# ModuleCarrier-Laird-BL600-v1_1.net
KiCad netlist of a schematic drawn in EAGLE
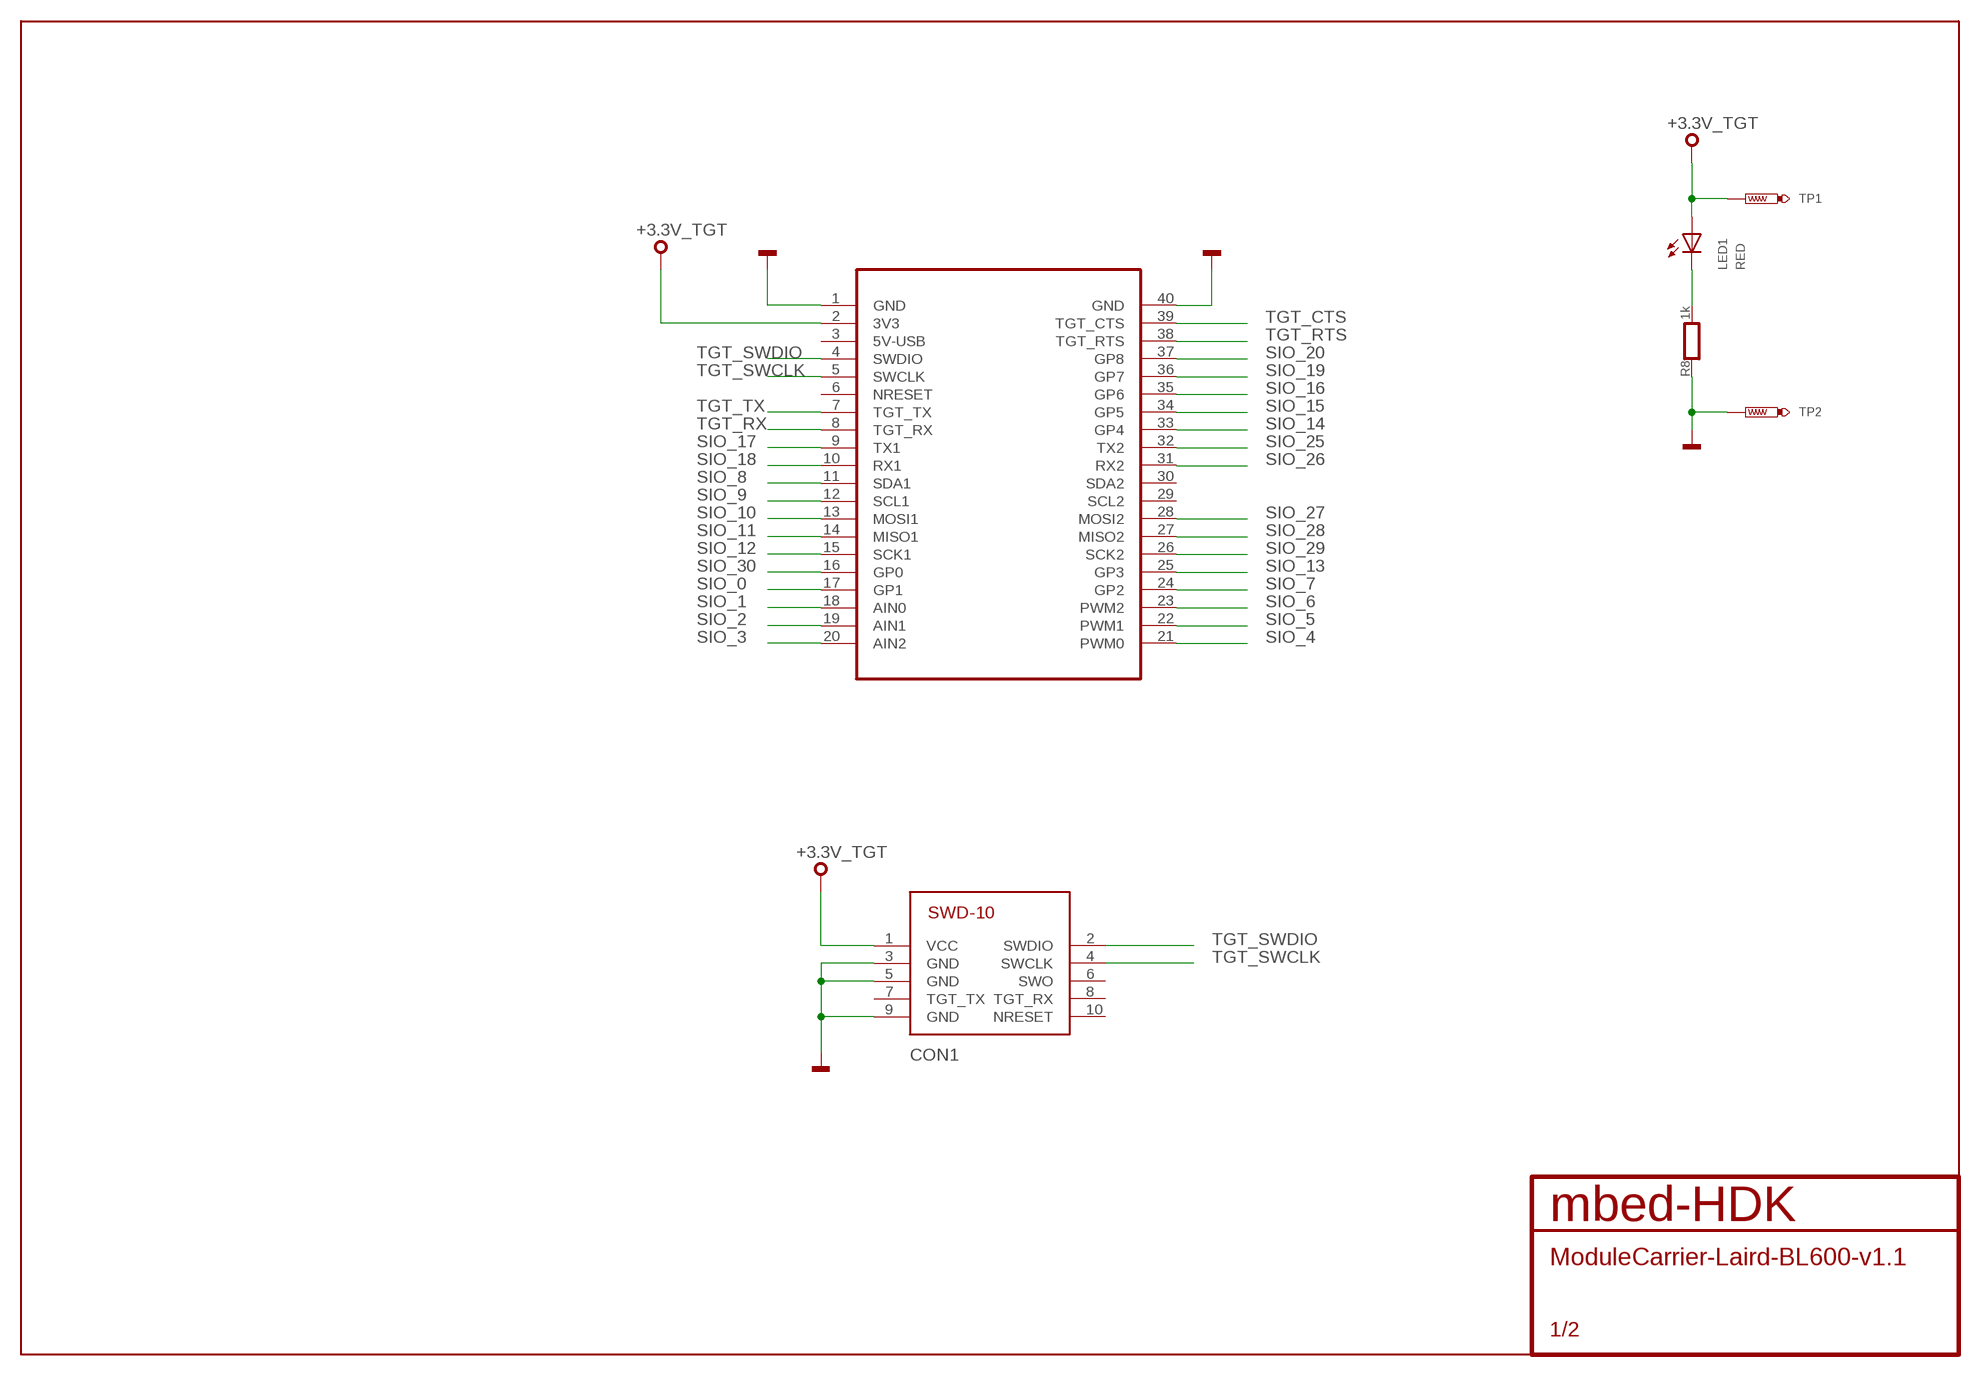
[diagram p0: schematic, sheet 1]
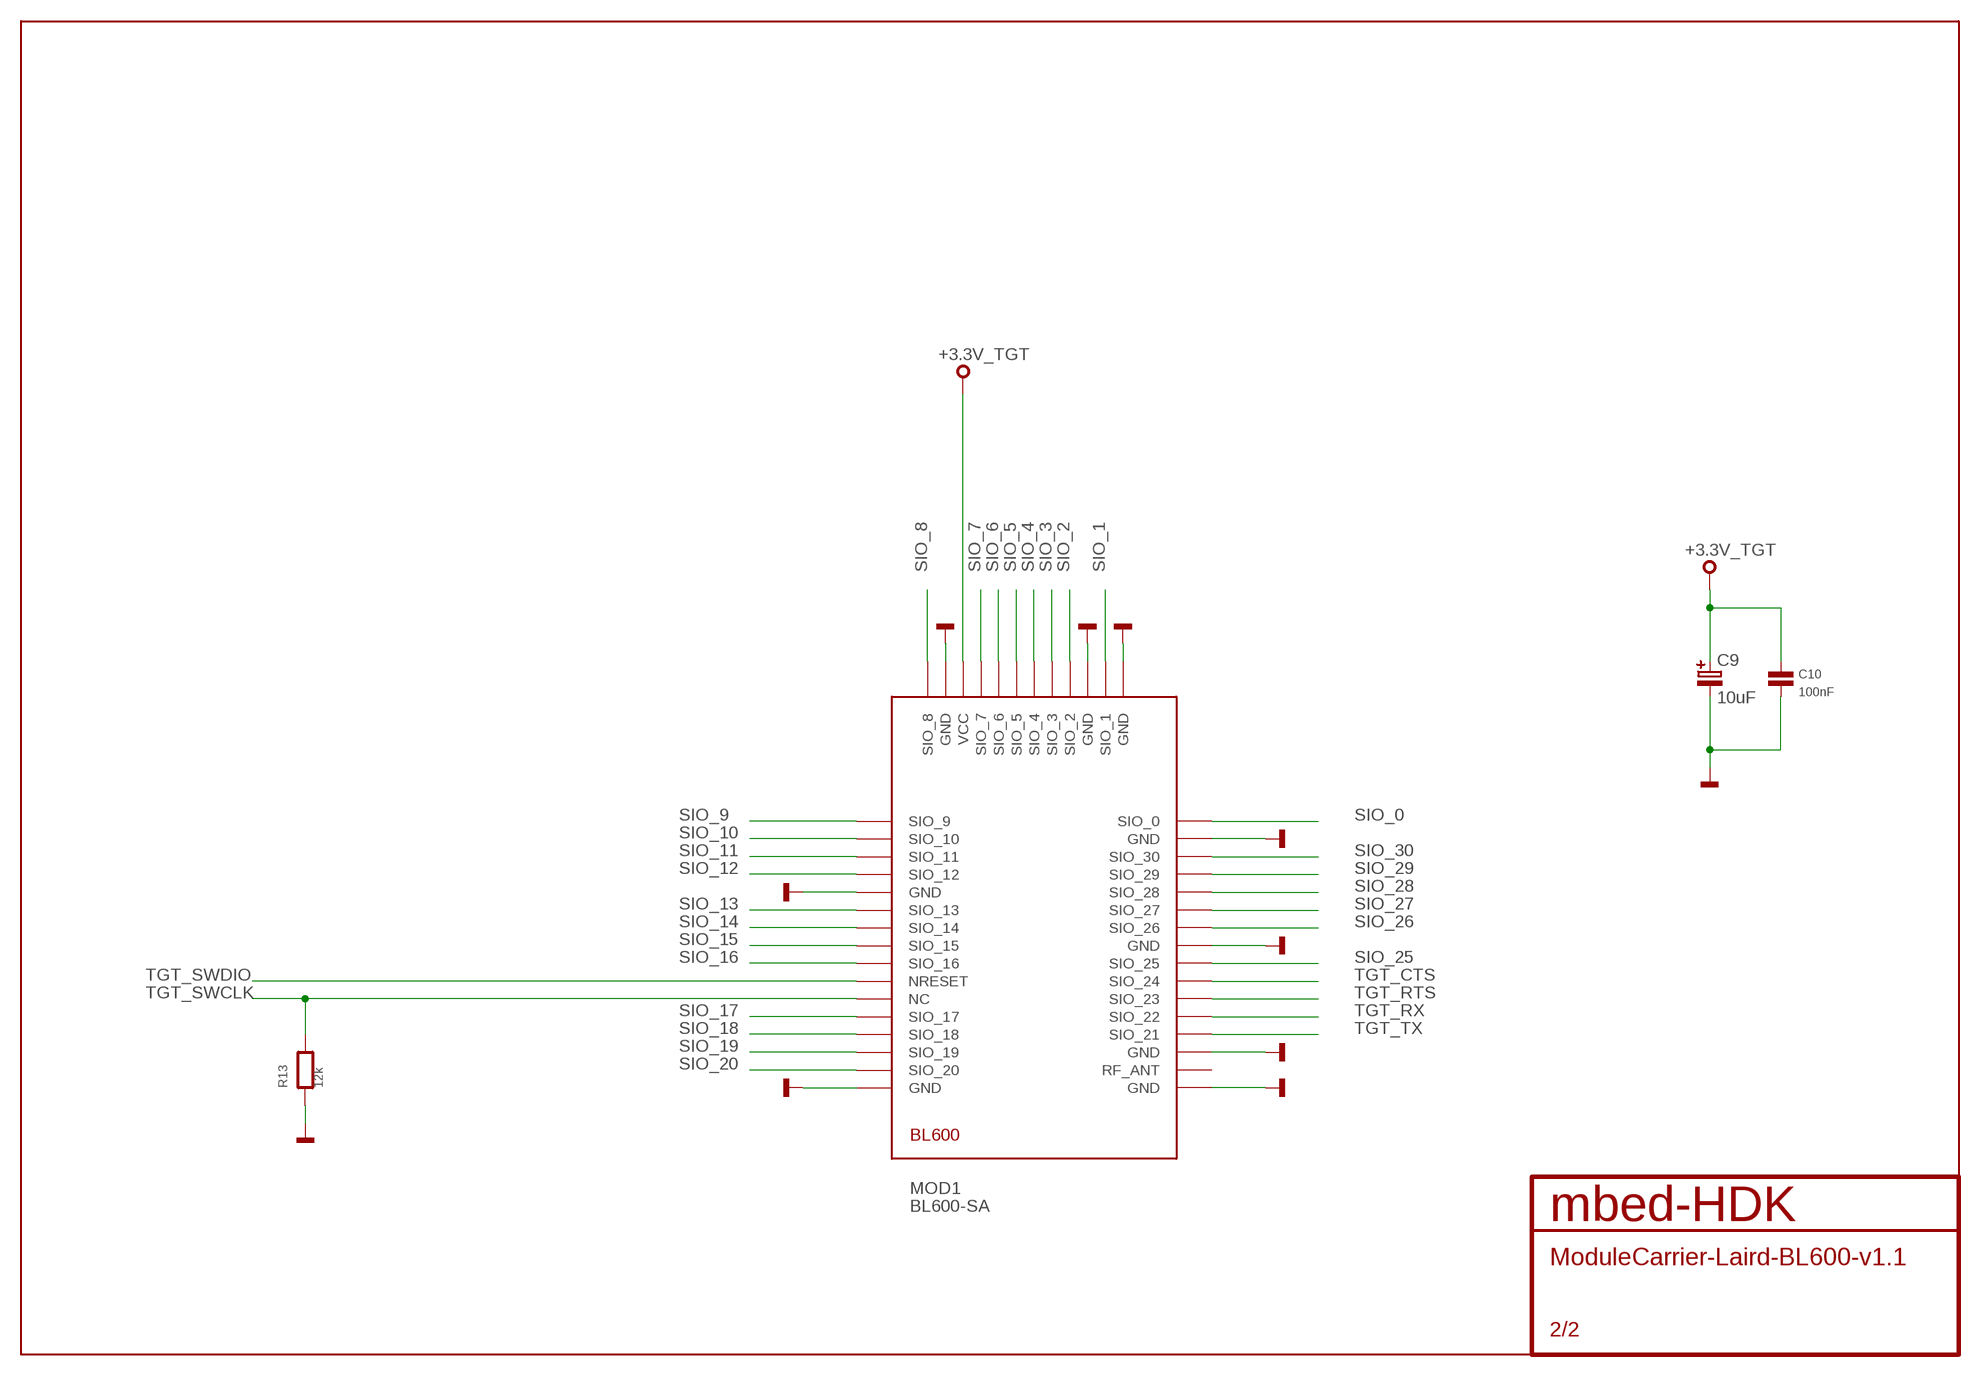
[diagram p1: schematic, sheet 2]

(export (version "E")
  (design (tool "Eeschema 10.0.6"))
  (components
    (comp (ref "CON1")
      (value "SWD-10/TC2050_SMD")
      (footprint "eagle-import:FTSH-105-02")
      (libsource (lib "eagle-import") (part "SWD-10/TC2050_SMD"))
    )
    (comp (ref "LED1")
      (value "RED")
      (footprint "eagle-import:CHIPLED_0603")
      (fields (field (name "MF") "Wurth Electronics Inc"))
      (libsource (lib "eagle-import") (part "SMD_LED0603"))
    )
    (comp (ref "R8")
      (value "1k")
      (footprint "eagle-import:0603")
      (libsource (lib "eagle-import") (part "RESISTOR0603"))
    )
    (comp (ref "TP1")
      (value "TEST-POINT-50R-PTH")
      (footprint "eagle-import:TP50-PTH")
      (libsource (lib "eagle-import") (part "TEST-POINT-50R-PTH"))
    )
    (comp (ref "TP2")
      (value "TEST-POINT-50R-PTH")
      (footprint "eagle-import:TP50-PTH")
      (libsource (lib "eagle-import") (part "TEST-POINT-50R-PTH"))
    )
    (comp (ref "U$1")
      (value "MODULE_DAUGHTER")
      (footprint "eagle-import:MODULE_DAUGHTER")
      (libsource (lib "eagle-import") (part "MODULE_DAUGHTER"))
    )
    (comp (ref "C9")
      (value "10uF")
      (footprint "eagle-import:CASE-B")
      (libsource (lib "eagle-import") (part "C-POLB"))
    )
    (comp (ref "C10")
      (value "100nF")
      (footprint "eagle-import:0603")
      (libsource (lib "eagle-import") (part "C0603"))
    )
    (comp (ref "MOD1")
      (value "BL600-SA")
      (footprint "eagle-import:BL600")
      (libsource (lib "eagle-import") (part "BL600-SA"))
    )
    (comp (ref "R13")
      (value "12k")
      (footprint "eagle-import:0603")
      (libsource (lib "eagle-import") (part "R0603"))
    )
  )
  (nets
    (net (code "1") (name "+3.3V_TGT") (class "Default")
      (node (ref "C10") (pin "1") (pinfunction "P$1_1") (pintype "passive"))
      (node (ref "C9") (pin "1") (pinfunction "1_1") (pintype "passive"))
      (node (ref "CON1") (pin "1") (pinfunction "VCC_1") (pintype "bidirectional"))
      (node (ref "LED1") (pin "A") (pinfunction "A_A") (pintype "passive"))
      (node (ref "MOD1") (pin "P$10") (pinfunction "VCC_P$10") (pintype "bidirectional"))
      (node (ref "TP1") (pin "TP") (pinfunction "TP_TP") (pintype "input"))
      (node (ref "U$1") (pin "2") (pinfunction "3V3_2") (pintype "bidirectional"))
    )
    (net (code "2") (name "GND") (class "Default")
      (node (ref "C10") (pin "2") (pinfunction "P$2_2") (pintype "passive"))
      (node (ref "C9") (pin "2") (pinfunction "2_2") (pintype "passive"))
      (node (ref "CON1") (pin "3") (pinfunction "GND_3") (pintype "bidirectional"))
      (node (ref "CON1") (pin "5") (pinfunction "GND_5") (pintype "bidirectional"))
      (node (ref "CON1") (pin "9") (pinfunction "GND_9") (pintype "bidirectional"))
      (node (ref "MOD1") (pin "P$1") (pinfunction "GND_P$1") (pintype "bidirectional"))
      (node (ref "MOD1") (pin "P$11") (pinfunction "GND_P$11") (pintype "bidirectional"))
      (node (ref "MOD1") (pin "P$17") (pinfunction "GND_P$17") (pintype "bidirectional"))
      (node (ref "MOD1") (pin "P$28") (pinfunction "GND_P$28") (pintype "bidirectional"))
      (node (ref "MOD1") (pin "P$29") (pinfunction "GND_P$29") (pintype "bidirectional"))
      (node (ref "MOD1") (pin "P$3") (pinfunction "GND_P$3") (pintype "bidirectional"))
      (node (ref "MOD1") (pin "P$31") (pinfunction "GND_P$31") (pintype "bidirectional"))
      (node (ref "MOD1") (pin "P$37") (pinfunction "GND_P$37") (pintype "bidirectional"))
      (node (ref "MOD1") (pin "P$43") (pinfunction "GND_P$43") (pintype "bidirectional"))
      (node (ref "R13") (pin "1") (pinfunction "P$1_1") (pintype "passive"))
      (node (ref "R8") (pin "1") (pinfunction "P$1_1") (pintype "passive"))
      (node (ref "TP2") (pin "TP") (pinfunction "TP_TP") (pintype "input"))
      (node (ref "U$1") (pin "1") (pinfunction "GND_1") (pintype "bidirectional"))
      (node (ref "U$1") (pin "40") (pinfunction "GND_40") (pintype "bidirectional"))
    )
    (net (code "3") (name "Net-(R8-P$2)") (class "Default")
      (node (ref "LED1") (pin "C") (pinfunction "C_C") (pintype "passive"))
      (node (ref "R8") (pin "2") (pinfunction "P$2_2") (pintype "passive"))
    )
    (net (code "4") (name "SIO_0") (class "Default")
      (node (ref "MOD1") (pin "P$44") (pinfunction "SIO_0_P$44") (pintype "bidirectional"))
      (node (ref "U$1") (pin "17") (pinfunction "GP1_17") (pintype "bidirectional"))
    )
    (net (code "5") (name "SIO_1") (class "Default")
      (node (ref "MOD1") (pin "P$2") (pinfunction "SIO_1_P$2") (pintype "bidirectional"))
      (node (ref "U$1") (pin "18") (pinfunction "AIN0_18") (pintype "bidirectional"))
    )
    (net (code "6") (name "SIO_2") (class "Default")
      (node (ref "MOD1") (pin "P$4") (pinfunction "SIO_2_P$4") (pintype "bidirectional"))
      (node (ref "U$1") (pin "19") (pinfunction "AIN1_19") (pintype "bidirectional"))
    )
    (net (code "7") (name "SIO_3") (class "Default")
      (node (ref "MOD1") (pin "P$5") (pinfunction "SIO_3_P$5") (pintype "bidirectional"))
      (node (ref "U$1") (pin "20") (pinfunction "AIN2_20") (pintype "bidirectional"))
    )
    (net (code "8") (name "SIO_4") (class "Default")
      (node (ref "MOD1") (pin "P$6") (pinfunction "SIO_4_P$6") (pintype "bidirectional"))
      (node (ref "U$1") (pin "21") (pinfunction "PWM0_21") (pintype "bidirectional"))
    )
    (net (code "9") (name "SIO_5") (class "Default")
      (node (ref "MOD1") (pin "P$7") (pinfunction "SIO_5_P$7") (pintype "bidirectional"))
      (node (ref "U$1") (pin "22") (pinfunction "PWM1_22") (pintype "bidirectional"))
    )
    (net (code "10") (name "SIO_6") (class "Default")
      (node (ref "MOD1") (pin "P$8") (pinfunction "SIO_6_P$8") (pintype "bidirectional"))
      (node (ref "U$1") (pin "23") (pinfunction "PWM2_23") (pintype "bidirectional"))
    )
    (net (code "11") (name "SIO_7") (class "Default")
      (node (ref "MOD1") (pin "P$9") (pinfunction "SIO_7_P$9") (pintype "bidirectional"))
      (node (ref "U$1") (pin "24") (pinfunction "GP2_24") (pintype "bidirectional"))
    )
    (net (code "12") (name "SIO_8") (class "Default")
      (node (ref "MOD1") (pin "P$12") (pinfunction "SIO_8_P$12") (pintype "bidirectional"))
      (node (ref "U$1") (pin "11") (pinfunction "SDA1_11") (pintype "bidirectional"))
    )
    (net (code "13") (name "SIO_9") (class "Default")
      (node (ref "MOD1") (pin "P$13") (pinfunction "SIO_9_P$13") (pintype "bidirectional"))
      (node (ref "U$1") (pin "12") (pinfunction "SCL1_12") (pintype "bidirectional"))
    )
    (net (code "14") (name "SIO_10") (class "Default")
      (node (ref "MOD1") (pin "P$14") (pinfunction "SIO_10_P$14") (pintype "bidirectional"))
      (node (ref "U$1") (pin "13") (pinfunction "MOSI1_13") (pintype "bidirectional"))
    )
    (net (code "15") (name "SIO_11") (class "Default")
      (node (ref "MOD1") (pin "P$15") (pinfunction "SIO_11_P$15") (pintype "bidirectional"))
      (node (ref "U$1") (pin "14") (pinfunction "MISO1_14") (pintype "bidirectional"))
    )
    (net (code "16") (name "SIO_12") (class "Default")
      (node (ref "MOD1") (pin "P$16") (pinfunction "SIO_12_P$16") (pintype "bidirectional"))
      (node (ref "U$1") (pin "15") (pinfunction "SCK1_15") (pintype "bidirectional"))
    )
    (net (code "17") (name "SIO_13") (class "Default")
      (node (ref "MOD1") (pin "P$18") (pinfunction "SIO_13_P$18") (pintype "bidirectional"))
      (node (ref "U$1") (pin "25") (pinfunction "GP3_25") (pintype "bidirectional"))
    )
    (net (code "18") (name "SIO_14") (class "Default")
      (node (ref "MOD1") (pin "P$19") (pinfunction "SIO_14_P$19") (pintype "bidirectional"))
      (node (ref "U$1") (pin "33") (pinfunction "GP4_33") (pintype "bidirectional"))
    )
    (net (code "19") (name "SIO_15") (class "Default")
      (node (ref "MOD1") (pin "P$20") (pinfunction "SIO_15_P$20") (pintype "bidirectional"))
      (node (ref "U$1") (pin "34") (pinfunction "GP5_34") (pintype "bidirectional"))
    )
    (net (code "20") (name "SIO_16") (class "Default")
      (node (ref "MOD1") (pin "P$21") (pinfunction "SIO_16_P$21") (pintype "bidirectional"))
      (node (ref "U$1") (pin "35") (pinfunction "GP6_35") (pintype "bidirectional"))
    )
    (net (code "21") (name "SIO_17") (class "Default")
      (node (ref "MOD1") (pin "P$24") (pinfunction "SIO_17_P$24") (pintype "bidirectional"))
      (node (ref "U$1") (pin "9") (pinfunction "TX1_9") (pintype "bidirectional"))
    )
    (net (code "22") (name "SIO_18") (class "Default")
      (node (ref "MOD1") (pin "P$25") (pinfunction "SIO_18_P$25") (pintype "bidirectional"))
      (node (ref "U$1") (pin "10") (pinfunction "RX1_10") (pintype "bidirectional"))
    )
    (net (code "23") (name "SIO_19") (class "Default")
      (node (ref "MOD1") (pin "P$26") (pinfunction "SIO_19_P$26") (pintype "bidirectional"))
      (node (ref "U$1") (pin "36") (pinfunction "GP7_36") (pintype "bidirectional"))
    )
    (net (code "24") (name "SIO_20") (class "Default")
      (node (ref "MOD1") (pin "P$27") (pinfunction "SIO_20_P$27") (pintype "bidirectional"))
      (node (ref "U$1") (pin "37") (pinfunction "GP8_37") (pintype "bidirectional"))
    )
    (net (code "25") (name "SIO_25") (class "Default")
      (node (ref "MOD1") (pin "P$36") (pinfunction "SIO_25_P$36") (pintype "bidirectional"))
      (node (ref "U$1") (pin "32") (pinfunction "TX2_32") (pintype "bidirectional"))
    )
    (net (code "26") (name "SIO_26") (class "Default")
      (node (ref "MOD1") (pin "P$38") (pinfunction "SIO_26_P$38") (pintype "bidirectional"))
      (node (ref "U$1") (pin "31") (pinfunction "RX2_31") (pintype "bidirectional"))
    )
    (net (code "27") (name "SIO_27") (class "Default")
      (node (ref "MOD1") (pin "P$39") (pinfunction "SIO_27_P$39") (pintype "bidirectional"))
      (node (ref "U$1") (pin "28") (pinfunction "MOSI2_28") (pintype "bidirectional"))
    )
    (net (code "28") (name "SIO_28") (class "Default")
      (node (ref "MOD1") (pin "P$40") (pinfunction "SIO_28_P$40") (pintype "bidirectional"))
      (node (ref "U$1") (pin "27") (pinfunction "MISO2_27") (pintype "bidirectional"))
    )
    (net (code "29") (name "SIO_29") (class "Default")
      (node (ref "MOD1") (pin "P$41") (pinfunction "SIO_29_P$41") (pintype "bidirectional"))
      (node (ref "U$1") (pin "26") (pinfunction "SCK2_26") (pintype "bidirectional"))
    )
    (net (code "30") (name "SIO_30") (class "Default")
      (node (ref "MOD1") (pin "P$42") (pinfunction "SIO_30_P$42") (pintype "bidirectional"))
      (node (ref "U$1") (pin "16") (pinfunction "GP0_16") (pintype "bidirectional"))
    )
    (net (code "31") (name "TGT_CTS") (class "Default")
      (node (ref "MOD1") (pin "P$35") (pinfunction "SIO_24_P$35") (pintype "bidirectional"))
      (node (ref "U$1") (pin "39") (pinfunction "TGT_CTS_39") (pintype "bidirectional"))
    )
    (net (code "32") (name "TGT_RTS") (class "Default")
      (node (ref "MOD1") (pin "P$34") (pinfunction "SIO_23_P$34") (pintype "bidirectional"))
      (node (ref "U$1") (pin "38") (pinfunction "TGT_RTS_38") (pintype "bidirectional"))
    )
    (net (code "33") (name "TGT_RX") (class "Default")
      (node (ref "MOD1") (pin "P$33") (pinfunction "SIO_22_P$33") (pintype "bidirectional"))
      (node (ref "U$1") (pin "8") (pinfunction "TGT_RX_8") (pintype "bidirectional"))
    )
    (net (code "34") (name "TGT_SWCLK") (class "Default")
      (node (ref "CON1") (pin "4") (pinfunction "SWCLK_4") (pintype "bidirectional"))
      (node (ref "MOD1") (pin "P$23") (pinfunction "NC_P$23") (pintype "bidirectional"))
      (node (ref "R13") (pin "2") (pinfunction "P$2_2") (pintype "passive"))
      (node (ref "U$1") (pin "5") (pinfunction "SWCLK_5") (pintype "bidirectional"))
    )
    (net (code "35") (name "TGT_SWDIO") (class "Default")
      (node (ref "CON1") (pin "2") (pinfunction "SWDIO_2") (pintype "bidirectional"))
      (node (ref "MOD1") (pin "P$22") (pinfunction "NRESET_P$22") (pintype "bidirectional"))
      (node (ref "U$1") (pin "4") (pinfunction "SWDIO_4") (pintype "bidirectional"))
    )
    (net (code "36") (name "TGT_TX") (class "Default")
      (node (ref "MOD1") (pin "P$32") (pinfunction "SIO_21_P$32") (pintype "bidirectional"))
      (node (ref "U$1") (pin "7") (pinfunction "TGT_TX_7") (pintype "bidirectional"))
    )
    (net (code "37") (name "unconnected-(CON1-NRESET-Pad10)") (class "Default")
      (node (ref "CON1") (pin "10") (pinfunction "NRESET_10") (pintype "bidirectional"))
    )
    (net (code "38") (name "unconnected-(CON1-SWO-Pad6)") (class "Default")
      (node (ref "CON1") (pin "6") (pinfunction "SWO_6") (pintype "bidirectional"))
    )
    (net (code "39") (name "unconnected-(CON1-TGT_RX-Pad8)") (class "Default")
      (node (ref "CON1") (pin "8") (pinfunction "TGT_RX_8") (pintype "bidirectional"))
    )
    (net (code "40") (name "unconnected-(CON1-TGT_TX-Pad7)") (class "Default")
      (node (ref "CON1") (pin "7") (pinfunction "TGT_TX_7") (pintype "bidirectional"))
    )
    (net (code "41") (name "unconnected-(MOD1-RF_ANT-PadP$30)") (class "Default")
      (node (ref "MOD1") (pin "P$30") (pinfunction "RF_ANT_P$30") (pintype "bidirectional"))
    )
    (net (code "42") (name "unconnected-(U$1-5V-USB-Pad3)") (class "Default")
      (node (ref "U$1") (pin "3") (pinfunction "5V-USB_3") (pintype "bidirectional"))
    )
    (net (code "43") (name "unconnected-(U$1-NRESET-Pad6)") (class "Default")
      (node (ref "U$1") (pin "6") (pinfunction "NRESET_6") (pintype "bidirectional"))
    )
    (net (code "44") (name "unconnected-(U$1-SCL2-Pad29)") (class "Default")
      (node (ref "U$1") (pin "29") (pinfunction "SCL2_29") (pintype "bidirectional"))
    )
    (net (code "45") (name "unconnected-(U$1-SDA2-Pad30)") (class "Default")
      (node (ref "U$1") (pin "30") (pinfunction "SDA2_30") (pintype "bidirectional"))
    )
  )
)
